# Sheet1.net
KiCad netlist of a schematic drawn in Altium Designer
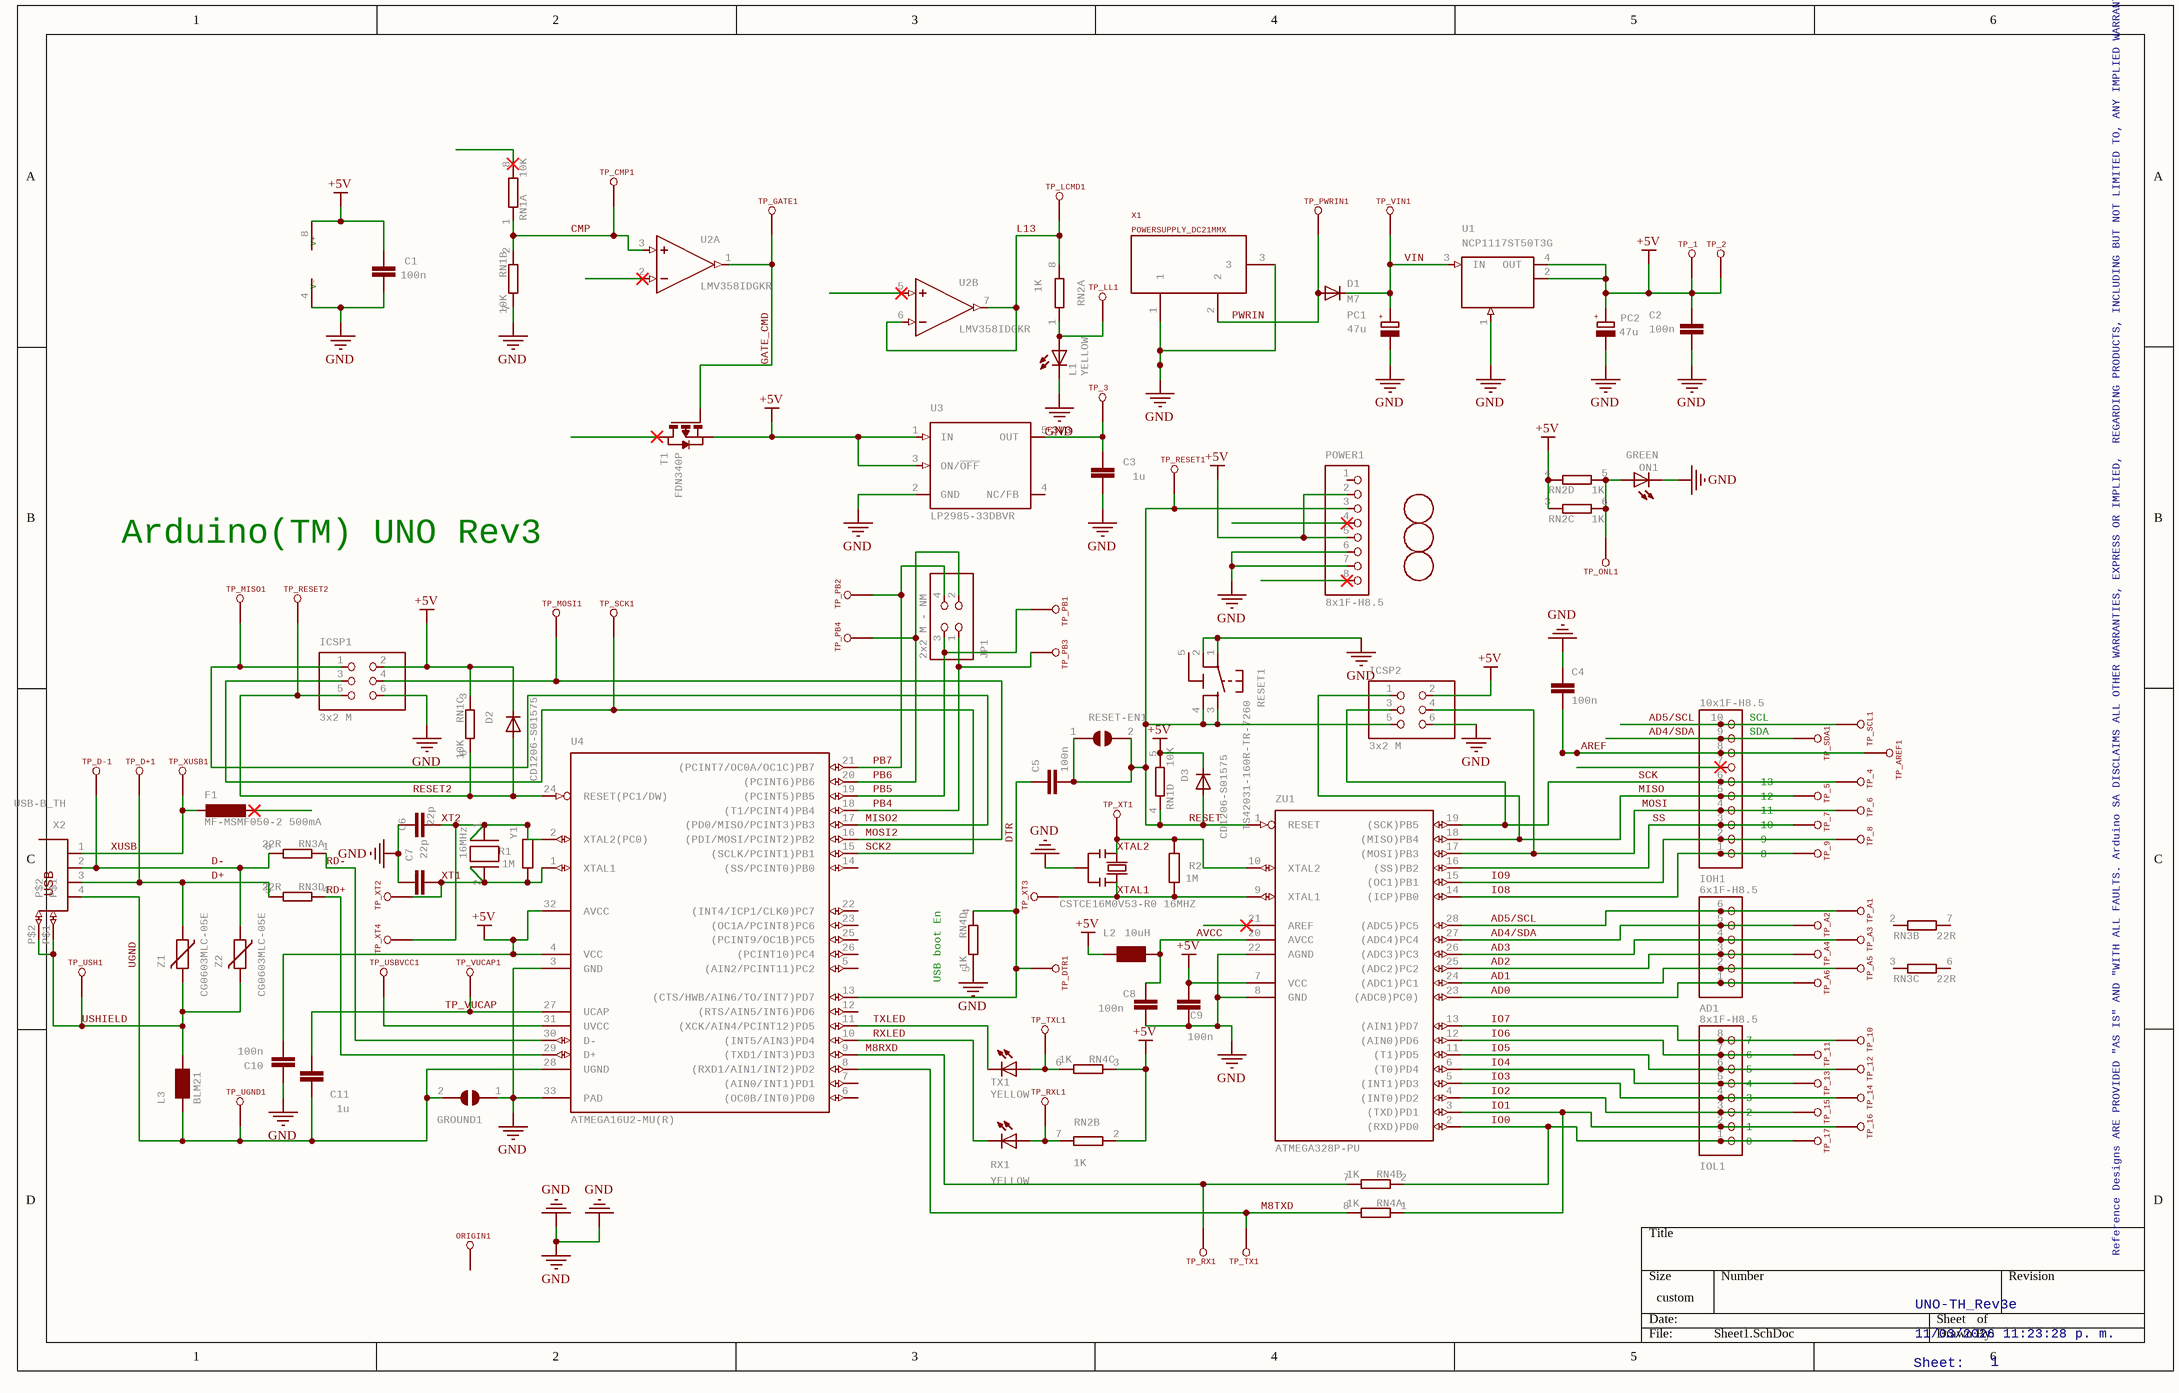
[diagram p0: Sheet1.SchDoc]

(export (version "E")
  (design (tool "Eeschema 10.0.6"))
  (components
    (comp (ref "AD1")
      (value "6x1F-H8.5")
      (footprint "1X06")
      (description "PIN HEADER")
      (libsource (lib "SmartPrj") (part "PINHD-1X6"))
    )
    (comp (ref "C1")
      (value "100n")
      (footprint "C0603-ROUND")
      (description "CAPACITOR, European symbol")
      (libsource (lib "") (part "C-EU0603-RND_1"))
    )
    (comp (ref "C2")
      (value "100n")
      (footprint "C0603-ROUND")
      (description "CAPACITOR, European symbol")
      (libsource (lib "") (part "C-EU0603-RND_2"))
    )
    (comp (ref "C3")
      (value "1u")
      (footprint "C0603-ROUND")
      (description "CAPACITOR, European symbol")
      (libsource (lib "") (part "C-EU0603-RND_1"))
    )
    (comp (ref "C4")
      (value "100n")
      (footprint "C0603-ROUND")
      (description "CAPACITOR, European symbol")
      (libsource (lib "SmartPrj") (part "C-EU0603-RND"))
    )
    (comp (ref "C5")
      (value "100n")
      (footprint "C0603-ROUND")
      (description "CAPACITOR, European symbol")
      (libsource (lib "") (part "C-EU0603-RND_1"))
    )
    (comp (ref "C6")
      (value "22p")
      (footprint "C0603-ROUND")
      (description "CAPACITOR, European symbol")
      (libsource (lib "SmartPrj") (part "C-EU0603-RND"))
    )
    (comp (ref "C7")
      (value "22p")
      (footprint "C0603-ROUND")
      (description "CAPACITOR, European symbol")
      (libsource (lib "SmartPrj") (part "C-EU0603-RND"))
    )
    (comp (ref "C8")
      (value "100n")
      (footprint "C0603-ROUND")
      (description "CAPACITOR, European symbol")
      (libsource (lib "") (part "C-EU0603-RND_2"))
    )
    (comp (ref "C9")
      (value "100n")
      (footprint "C0603-ROUND")
      (description "CAPACITOR, European symbol")
      (libsource (lib "") (part "C-EU0603-RND_2"))
    )
    (comp (ref "C10")
      (value "100n")
      (footprint "C0603-ROUND")
      (description "CAPACITOR, European symbol")
      (libsource (lib "") (part "C-EU0603-RND_3"))
    )
    (comp (ref "C11")
      (value "1u")
      (footprint "C0603-ROUND")
      (description "CAPACITOR, European symbol")
      (libsource (lib "") (part "C-EU0603-RND_3"))
    )
    (comp (ref "D1")
      (value "M7")
      (footprint "SMB")
      (description "DIODE")
      (libsource (lib "diode") (part "DIODE-SMB"))
    )
    (comp (ref "D2")
      (value "CD1206-S01575")
      (footprint "MINIMELF")
      (description "DIODE")
      (libsource (lib "diode") (part "DIODE-MINIMELF"))
    )
    (comp (ref "D3")
      (value "CD1206-S01575")
      (footprint "MINIMELF")
      (description "DIODE")
      (libsource (lib "diode") (part "DIODE-MINIMELF"))
    )
    (comp (ref "F1")
      (value "MF-MSMF050-2 500mA")
      (footprint "L1812")
      (description "INDUCTOR, European symbol")
      (libsource (lib "rcl") (part "L-EUL1812"))
    )
    (comp (ref "FD1")
      (value "FIDUCIALMOUNT")
      (footprint "FIDUCIA-MOUNT")
      (libsource (lib "SmartPrj") (part "FIDUCIALMOUNT"))
    )
    (comp (ref "FD2")
      (value "FIDUCIALMOUNT")
      (footprint "FIDUCIA-MOUNT")
      (libsource (lib "SmartPrj") (part "FIDUCIALMOUNT"))
    )
    (comp (ref "FD3")
      (value "FIDUCIALMOUNT")
      (footprint "FIDUCIA-MOUNT")
      (libsource (lib "SmartPrj") (part "FIDUCIALMOUNT"))
    )
    (comp (ref "GROUND1")
      (value "SJ")
      (footprint "SJ")
      (description "SMD solder JUMPER")
      (libsource (lib "jumper") (part "SJ"))
    )
    (comp (ref "ICSP1")
      (value "3x2 M")
      (footprint "2X03")
      (description "PIN HEADER")
      (libsource (lib "SmartPrj") (part "PINHD-2X3"))
    )
    (comp (ref "ICSP2")
      (value "3x2 M")
      (footprint "2X03")
      (description "PIN HEADER")
      (libsource (lib "SmartPrj") (part "PINHD-2X3"))
    )
    (comp (ref "IOH1")
      (value "10x1F-H8.5")
      (footprint "1X10")
      (description "PIN HEADER")
      (libsource (lib "SmartPrj") (part "PINHD-1X10_ARD"))
    )
    (comp (ref "IOL1")
      (value "8x1F-H8.5")
      (footprint "1X08")
      (description "PIN HEADER")
      (libsource (lib "SmartPrj") (part "PINHD-1X8"))
    )
    (comp (ref "JP1")
      (value "2x2 M - NM")
      (footprint "2X02")
      (description "PIN HEADER")
      (libsource (lib "SmartPrj") (part "PINHD-2X2"))
    )
    (comp (ref "L1")
      (value "YELLOW")
      (footprint "CHIP-LED0805")
      (libsource (lib "led") (part "LEDCHIP-LED0805"))
    )
    (comp (ref "L2")
      (value "10uH")
      (footprint "0805")
      (description "10uH 0805")
      (fields (field (name "PART_NUMBER") "CV201210-100K"))
      (libsource (lib "Induttanze") (part "0715_CV201210-100K"))
    )
    (comp (ref "L3")
      (value "BLM21")
      (footprint "0805")
      (libsource (lib "wuerth-elektronik") (part "WE-CBF_0805"))
    )
    (comp (ref "ON1")
      (value "GREEN")
      (footprint "CHIP-LED0805")
      (libsource (lib "led") (part "LEDCHIP-LED0805"))
    )
    (comp (ref "ORIGIN1") (value "TP_SP") (footprint "TP-SP") (libsource (lib "SmartPrj") (part "TP_SP")))
    (comp (ref "PC1")
      (value "47u")
      (footprint "PANASONIC_D")
      (description "POLARIZED CAPACITOR, European symbol")
      (fields (field (name "+") "+"))
      (libsource (lib "rcl") (part "CPOL-EUD"))
    )
    (comp (ref "PC2")
      (value "47u")
      (footprint "PANASONIC_D")
      (description "POLARIZED CAPACITOR, European symbol")
      (fields (field (name "+") "+"))
      (libsource (lib "rcl") (part "CPOL-EUD"))
    )
    (comp (ref "POWER1")
      (value "8x1F-H8.5")
      (footprint "1X08")
      (description "PIN HEADER")
      (libsource (lib "SmartPrj") (part "PINHD-1X8"))
    )
    (comp (ref "R1")
      (value "1M")
      (footprint "R0603-ROUND")
      (description "RESISTOR, European symbol")
      (libsource (lib "SmartPrj") (part "R-EU_R0603"))
    )
    (comp (ref "R2")
      (value "1M")
      (footprint "R0603-ROUND")
      (description "RESISTOR, European symbol")
      (libsource (lib "SmartPrj") (part "R-EU_R0603"))
    )
    (comp (ref "RESET-EN1")
      (value "SJ")
      (footprint "SJ")
      (description "SMD solder JUMPER")
      (libsource (lib "jumper") (part "SJ"))
    )
    (comp (ref "RESET1")
      (value "TS42031-160R-TR-7260")
      (footprint "TS42")
      (description "TS42 Dongnan Electronics Tact switch VDC 12V - 50mA")
      (libsource (lib "SmartPrj") (part "TS42"))
    )
    (comp (ref "RN1")
      (value "10K")
      (footprint "CAY16")
      (description "Array Chip Resistor   Source: RS Component / Phycomp")
      (libsource (lib "resistor-dil") (part "4R-NCAY16"))
    )
    (comp (ref "RN2")
      (value "1K")
      (footprint "CAY16")
      (description "Array Chip Resistor   Source: RS Component / Phycomp")
      (libsource (lib "resistor-dil") (part "4R-NCAY16"))
    )
    (comp (ref "RN3")
      (value "22R")
      (footprint "CAY16")
      (description "Array Chip Resistor   Source: RS Component / Phycomp")
      (libsource (lib "resistor-dil") (part "4R-NCAY16"))
    )
    (comp (ref "RN4")
      (value "1K")
      (footprint "CAY16")
      (description "Array Chip Resistor   Source: RS Component / Phycomp")
      (libsource (lib "resistor-dil") (part "4R-NCAY16"))
    )
    (comp (ref "RX1")
      (value "YELLOW")
      (footprint "CHIP-LED0805")
      (libsource (lib "led") (part "LEDCHIP-LED0805"))
    )
    (comp (ref "T1")
      (value "FDN340P")
      (footprint "SOT-23")
      (description "MOS FET")
      (libsource (lib "zetex") (part "PMOSSOT23"))
    )
    (comp (ref "TP_1") (value "TP_SP") (footprint "TP-SP") (libsource (lib "SmartPrj") (part "TP_SP")))
    (comp (ref "TP_2") (value "TP_SP") (footprint "TP-SP") (libsource (lib "SmartPrj") (part "TP_SP")))
    (comp (ref "TP_3") (value "TP_SP") (footprint "TP-SP") (libsource (lib "SmartPrj") (part "TP_SP")))
    (comp (ref "TP_4") (value "TP_SP") (footprint "TP-SP") (libsource (lib "SmartPrj") (part "TP_SP")))
    (comp (ref "TP_5") (value "TP_SP") (footprint "TP-SP") (libsource (lib "SmartPrj") (part "TP_SP")))
    (comp (ref "TP_6") (value "TP_SP") (footprint "TP-SP") (libsource (lib "SmartPrj") (part "TP_SP")))
    (comp (ref "TP_7") (value "TP_SP") (footprint "TP-SP") (libsource (lib "SmartPrj") (part "TP_SP")))
    (comp (ref "TP_8") (value "TP_SP") (footprint "TP-SP") (libsource (lib "SmartPrj") (part "TP_SP")))
    (comp (ref "TP_9") (value "TP_SP") (footprint "TP-SP") (libsource (lib "SmartPrj") (part "TP_SP")))
    (comp (ref "TP_10") (value "TP_SP") (footprint "TP-SP") (libsource (lib "SmartPrj") (part "TP_SP")))
    (comp (ref "TP_11") (value "TP_SP") (footprint "TP-SP") (libsource (lib "SmartPrj") (part "TP_SP")))
    (comp (ref "TP_12") (value "TP_SP") (footprint "TP-SP") (libsource (lib "SmartPrj") (part "TP_SP")))
    (comp (ref "TP_13") (value "TP_SP") (footprint "TP-SP") (libsource (lib "SmartPrj") (part "TP_SP")))
    (comp (ref "TP_14") (value "TP_SP") (footprint "TP-SP") (libsource (lib "SmartPrj") (part "TP_SP")))
    (comp (ref "TP_15") (value "TP_SP") (footprint "TP-SP") (libsource (lib "SmartPrj") (part "TP_SP")))
    (comp (ref "TP_16") (value "TP_SP") (footprint "TP-SP") (libsource (lib "SmartPrj") (part "TP_SP")))
    (comp (ref "TP_17") (value "TP_SP") (footprint "TP-SP") (libsource (lib "SmartPrj") (part "TP_SP")))
    (comp (ref "TP_A1") (value "TP_SP") (footprint "TP-SP") (libsource (lib "SmartPrj") (part "TP_SP")))
    (comp (ref "TP_A2") (value "TP_SP") (footprint "TP-SP") (libsource (lib "SmartPrj") (part "TP_SP")))
    (comp (ref "TP_A3") (value "TP_SP") (footprint "TP-SP") (libsource (lib "SmartPrj") (part "TP_SP")))
    (comp (ref "TP_A4") (value "TP_SP") (footprint "TP-SP") (libsource (lib "SmartPrj") (part "TP_SP")))
    (comp (ref "TP_A5") (value "TP_SP") (footprint "TP-SP") (libsource (lib "SmartPrj") (part "TP_SP")))
    (comp (ref "TP_A6") (value "TP_SP") (footprint "TP-SP") (libsource (lib "SmartPrj") (part "TP_SP")))
    (comp (ref "TP_AREF1") (value "TP_SP") (footprint "TP-SP") (libsource (lib "SmartPrj") (part "TP_SP")))
    (comp (ref "TP_CMP1") (value "TP_SP") (footprint "TP-SP") (libsource (lib "SmartPrj") (part "TP_SP")))
    (comp (ref "TP_D+1") (value "TP_SP") (footprint "TP-SP") (libsource (lib "SmartPrj") (part "TP_SP")))
    (comp (ref "TP_D-1") (value "TP_SP") (footprint "TP-SP") (libsource (lib "SmartPrj") (part "TP_SP")))
    (comp (ref "TP_DTR1") (value "TP_SP") (footprint "TP-SP") (libsource (lib "SmartPrj") (part "TP_SP")))
    (comp (ref "TP_GATE1") (value "TP_SP") (footprint "TP-SP") (libsource (lib "SmartPrj") (part "TP_SP")))
    (comp (ref "TP_LCMD1") (value "TP_SP") (footprint "TP-SP") (libsource (lib "SmartPrj") (part "TP_SP")))
    (comp (ref "TP_LL1") (value "TP_SP") (footprint "TP-SP") (libsource (lib "SmartPrj") (part "TP_SP")))
    (comp (ref "TP_MISO1") (value "TP_SP") (footprint "TP-SP") (libsource (lib "SmartPrj") (part "TP_SP")))
    (comp (ref "TP_MOSI1") (value "TP_SP") (footprint "TP-SP") (libsource (lib "SmartPrj") (part "TP_SP")))
    (comp (ref "TP_ONL1") (value "TP_SP") (footprint "TP-SP") (libsource (lib "SmartPrj") (part "TP_SP")))
    (comp (ref "TP_PB1") (value "TP_SP") (footprint "TP-SP") (libsource (lib "SmartPrj") (part "TP_SP")))
    (comp (ref "TP_PB2") (value "TP_SP") (footprint "TP-SP") (libsource (lib "SmartPrj") (part "TP_SP")))
    (comp (ref "TP_PB3") (value "TP_SP") (footprint "TP-SP") (libsource (lib "SmartPrj") (part "TP_SP")))
    (comp (ref "TP_PB4") (value "TP_SP") (footprint "TP-SP") (libsource (lib "SmartPrj") (part "TP_SP")))
    (comp (ref "TP_PWRIN1") (value "TP_SP") (footprint "TP-SP") (libsource (lib "SmartPrj") (part "TP_SP")))
    (comp (ref "TP_RESET1") (value "TP_SP") (footprint "TP-SP") (libsource (lib "SmartPrj") (part "TP_SP")))
    (comp (ref "TP_RESET2") (value "TP_SP") (footprint "TP-SP") (libsource (lib "SmartPrj") (part "TP_SP")))
    (comp (ref "TP_RX1") (value "TP_SP") (footprint "TP-SP") (libsource (lib "SmartPrj") (part "TP_SP")))
    (comp (ref "TP_RXL1") (value "TP_SP") (footprint "TP-SP") (libsource (lib "SmartPrj") (part "TP_SP")))
    (comp (ref "TP_SCK1") (value "TP_SP") (footprint "TP-SP") (libsource (lib "SmartPrj") (part "TP_SP")))
    (comp (ref "TP_SCL1") (value "TP_SP") (footprint "TP-SP") (libsource (lib "SmartPrj") (part "TP_SP")))
    (comp (ref "TP_SDA1") (value "TP_SP") (footprint "TP-SP") (libsource (lib "SmartPrj") (part "TP_SP")))
    (comp (ref "TP_TX1") (value "TP_SP") (footprint "TP-SP") (libsource (lib "SmartPrj") (part "TP_SP")))
    (comp (ref "TP_TXL1") (value "TP_SP") (footprint "TP-SP") (libsource (lib "SmartPrj") (part "TP_SP")))
    (comp (ref "TP_UGND1") (value "TP_SP") (footprint "TP-SP") (libsource (lib "SmartPrj") (part "TP_SP")))
    (comp (ref "TP_USBVCC1") (value "TP_SP") (footprint "TP-SP") (libsource (lib "SmartPrj") (part "TP_SP")))
    (comp (ref "TP_USH1") (value "TP_SP") (footprint "TP-SP") (libsource (lib "SmartPrj") (part "TP_SP")))
    (comp (ref "TP_VIN1") (value "TP_SP") (footprint "TP-SP") (libsource (lib "SmartPrj") (part "TP_SP")))
    (comp (ref "TP_VUCAP1") (value "TP_SP") (footprint "TP-SP") (libsource (lib "SmartPrj") (part "TP_SP")))
    (comp (ref "TP_XT1") (value "TP_SP") (footprint "TP-SP") (libsource (lib "SmartPrj") (part "TP_SP")))
    (comp (ref "TP_XT2") (value "TP_SP") (footprint "TP-SP") (libsource (lib "SmartPrj") (part "TP_SP")))
    (comp (ref "TP_XT3") (value "TP_SP") (footprint "TP-SP") (libsource (lib "SmartPrj") (part "TP_SP")))
    (comp (ref "TP_XT4") (value "TP_SP") (footprint "TP-SP") (libsource (lib "SmartPrj") (part "TP_SP")))
    (comp (ref "TP_XUSB1") (value "TP_SP") (footprint "TP-SP") (libsource (lib "SmartPrj") (part "TP_SP")))
    (comp (ref "TX1")
      (value "YELLOW")
      (footprint "CHIP-LED0805")
      (libsource (lib "led") (part "LEDCHIP-LED0805"))
    )
    (comp (ref "U1")
      (value "NCP1117ST50T3G")
      (footprint "SOT223")
      (libsource (lib "linear") (part "MC33269ST*"))
    )
    (comp (ref "U2")
      (value "LMV358IDGKR")
      (footprint "MSOP08")
      (fields (field (name "V+") "V+") (field (name "V-") "V-"))
      (libsource (lib "linear") (part "LMV358?*MM"))
    )
    (comp (ref "U3")
      (value "LP2985-33DBVR")
      (footprint "SOT23-DBV")
      (libsource (lib "SmartPrj") (part "LP2985-XXDBVR"))
    )
    (comp (ref "U4")
      (value "ATMEGA16U2-MU(R)")
      (footprint "MLF32")
      (libsource (lib "SmartPrj") (part "ATMEGA16U2-MU"))
    )
    (comp (ref "X1")
      (value "POWERSUPPLY_DC21MMX")
      (footprint "POWERSUPPLY_DC-21MM")
      (libsource (lib "SmartPrj") (part "POWERSUPPLY_DC21MMX"))
    )
    (comp (ref "X2")
      (value "USB-B_TH")
      (footprint "PN61729")
      (description "BERG USB connector")
      (fields (field (name "USB") "USB"))
      (libsource (lib "SmartPrj") (part "PN61729"))
    )
    (comp (ref "Y1")
      (value "16MHz")
      (footprint "QS")
      (description "CRYSTAL")
      (libsource (lib "SmartPrj") (part "XTAL/S"))
    )
    (comp (ref "Y2")
      (value "CSTCE16M0V53-R0 16MHZ")
      (footprint "RESONATOR")
      (libsource (lib "SmartPrj") (part "RESONATORMU"))
    )
    (comp (ref "Z1")
      (value "CG0603MLC-05E")
      (footprint "CT/CN0603")
      (description "VARISTOR")
      (libsource (lib "varistor") (part "VARISTORCN0603"))
    )
    (comp (ref "Z2")
      (value "CG0603MLC-05E")
      (footprint "CT/CN0603")
      (description "VARISTOR")
      (libsource (lib "varistor") (part "VARISTORCN0603"))
    )
    (comp (ref "ZU1")
      (value "ATMEGA328P-PU")
      (footprint "DIL28-3")
      (description "MICROCONTROLLER   4 Kbytes FLASH   128 bytes SRAM   256 bytes EEPROM   UART   6-channel 10 bit ADC")
      (libsource (lib "SmartPrj") (part "ATMEGA328P-PU"))
    )
  )
  (nets
    (net (code "1") (name "+5V") (class "Default")
      (node (ref "C1") (pin "2") (pinfunction "2_2") (pintype "passive"))
      (node (ref "C10") (pin "1") (pinfunction "1_1") (pintype "passive"))
      (node (ref "C2") (pin "2") (pinfunction "2_2") (pintype "passive"))
      (node (ref "C9") (pin "2") (pinfunction "2_2") (pintype "passive"))
      (node (ref "D2") (pin "C") (pinfunction "C_C") (pintype "passive"))
      (node (ref "D3") (pin "C") (pinfunction "C_C") (pintype "passive"))
      (node (ref "ICSP1") (pin "2") (pinfunction "2_2") (pintype "passive"))
      (node (ref "ICSP2") (pin "2") (pinfunction "2_2") (pintype "passive"))
      (node (ref "L2") (pin "1") (pinfunction "1_1") (pintype "passive"))
      (node (ref "PC2") (pin "+") (pinfunction "+_+") (pintype "passive"))
      (node (ref "POWER1") (pin "2") (pinfunction "2_2") (pintype "passive"))
      (node (ref "POWER1") (pin "5") (pinfunction "5_5") (pintype "passive"))
      (node (ref "RN1") (pin "3") (pinfunction "1_3") (pintype "passive"))
      (node (ref "RN1") (pin "5") (pinfunction "2_5") (pintype "passive"))
      (node (ref "RN2") (pin "2") (pinfunction "1_2") (pintype "passive"))
      (node (ref "RN2") (pin "3") (pinfunction "1_3") (pintype "passive"))
      (node (ref "RN2") (pin "4") (pinfunction "1_4") (pintype "passive"))
      (node (ref "RN4") (pin "3") (pinfunction "1_3") (pintype "passive"))
      (node (ref "T1") (pin "2") (pinfunction "S_2") (pintype "passive"))
      (node (ref "TP_1") (pin "X") (pinfunction "TESTP_X") (pintype "passive"))
      (node (ref "TP_2") (pin "X") (pinfunction "TESTP_X") (pintype "passive"))
      (node (ref "U1") (pin "2") (pinfunction "OUT_2") (pintype "passive"))
      (node (ref "U1") (pin "4") (pinfunction "OUT_4") (pintype "passive"))
      (node (ref "U2") (pin "8") (pinfunction "V+_8") (pintype "power_in"))
      (node (ref "U3") (pin "1") (pinfunction "IN_1") (pintype "input"))
      (node (ref "U3") (pin "3") (pinfunction "ON/~{OFF}_3") (pintype "input"))
      (node (ref "U4") (pin "32") (pinfunction "AVCC_32") (pintype "power_in"))
      (node (ref "U4") (pin "4") (pinfunction "VCC_4") (pintype "power_in"))
      (node (ref "ZU1") (pin "7") (pinfunction "VCC_7") (pintype "power_in"))
    )
    (net (code "2") (name "/+3V3") (class "Default")
      (node (ref "C3") (pin "2") (pinfunction "2_2") (pintype "passive"))
      (node (ref "TP_3") (pin "X") (pinfunction "TESTP_X") (pintype "passive"))
      (node (ref "U3") (pin "5") (pinfunction "OUT_5") (pintype "passive"))
    )
    (net (code "3") (name "/AD0") (class "Default")
      (node (ref "AD1") (pin "1") (pinfunction "1_1") (pintype "passive"))
      (node (ref "TP_A6") (pin "X") (pinfunction "TESTP_X") (pintype "passive"))
      (node (ref "ZU1") (pin "23") (pinfunction "(ADC0)PC0)_23") (pintype "bidirectional"))
    )
    (net (code "4") (name "/AD1") (class "Default")
      (node (ref "AD1") (pin "2") (pinfunction "2_2") (pintype "passive"))
      (node (ref "TP_A5") (pin "X") (pinfunction "TESTP_X") (pintype "passive"))
      (node (ref "ZU1") (pin "24") (pinfunction "(ADC1)PC1_24") (pintype "bidirectional"))
    )
    (net (code "5") (name "/AD2") (class "Default")
      (node (ref "AD1") (pin "3") (pinfunction "3_3") (pintype "passive"))
      (node (ref "TP_A4") (pin "X") (pinfunction "TESTP_X") (pintype "passive"))
      (node (ref "ZU1") (pin "25") (pinfunction "(ADC2)PC2_25") (pintype "bidirectional"))
    )
    (net (code "6") (name "/AD3") (class "Default")
      (node (ref "AD1") (pin "4") (pinfunction "4_4") (pintype "passive"))
      (node (ref "TP_A3") (pin "X") (pinfunction "TESTP_X") (pintype "passive"))
      (node (ref "ZU1") (pin "26") (pinfunction "(ADC3)PC3_26") (pintype "bidirectional"))
    )
    (net (code "7") (name "/AD4{slash}SDA") (class "Default")
      (node (ref "AD1") (pin "5") (pinfunction "5_5") (pintype "passive"))
      (node (ref "IOH1") (pin "9") (pinfunction "9_9") (pintype "passive"))
      (node (ref "TP_A2") (pin "X") (pinfunction "TESTP_X") (pintype "passive"))
      (node (ref "TP_SDA1") (pin "X") (pinfunction "TESTP_X") (pintype "passive"))
      (node (ref "ZU1") (pin "27") (pinfunction "(ADC4)PC4_27") (pintype "bidirectional"))
    )
    (net (code "8") (name "/AD5{slash}SCL") (class "Default")
      (node (ref "AD1") (pin "6") (pinfunction "6_6") (pintype "passive"))
      (node (ref "IOH1") (pin "10") (pinfunction "10_10") (pintype "passive"))
      (node (ref "TP_A1") (pin "X") (pinfunction "TESTP_X") (pintype "passive"))
      (node (ref "TP_SCL1") (pin "X") (pinfunction "TESTP_X") (pintype "passive"))
      (node (ref "ZU1") (pin "28") (pinfunction "(ADC5)PC5_28") (pintype "bidirectional"))
    )
    (net (code "9") (name "/AREF") (class "Default")
      (node (ref "C4") (pin "2") (pinfunction "2_2") (pintype "passive"))
      (node (ref "IOH1") (pin "8") (pinfunction "8_8") (pintype "passive"))
      (node (ref "TP_AREF1") (pin "X") (pinfunction "TESTP_X") (pintype "passive"))
    )
    (net (code "10") (name "/AVCC") (class "Default")
      (node (ref "C8") (pin "2") (pinfunction "2_2") (pintype "passive"))
      (node (ref "L2") (pin "2") (pinfunction "2_2") (pintype "passive"))
      (node (ref "ZU1") (pin "20") (pinfunction "AVCC_20") (pintype "power_in"))
    )
    (net (code "11") (name "/CMP") (class "Default")
      (node (ref "RN1") (pin "1") (pinfunction "1_1") (pintype "passive"))
      (node (ref "RN1") (pin "2") (pinfunction "1_2") (pintype "passive"))
      (node (ref "TP_CMP1") (pin "X") (pinfunction "TESTP_X") (pintype "passive"))
      (node (ref "U2") (pin "3") (pinfunction "+IN_3") (pintype "input"))
    )
    (net (code "12") (name "/D+") (class "Default")
      (node (ref "RN3") (pin "5") (pinfunction "2_5") (pintype "passive"))
      (node (ref "TP_D+1") (pin "X") (pinfunction "TESTP_X") (pintype "passive"))
      (node (ref "X2") (pin "3") (pinfunction "3_3") (pintype "bidirectional"))
      (node (ref "Z1") (pin "1") (pinfunction "1_1") (pintype "passive"))
    )
    (net (code "13") (name "/D-") (class "Default")
      (node (ref "RN3") (pin "8") (pinfunction "2_8") (pintype "passive"))
      (node (ref "TP_D-1") (pin "X") (pinfunction "TESTP_X") (pintype "passive"))
      (node (ref "X2") (pin "2") (pinfunction "2_2") (pintype "bidirectional"))
      (node (ref "Z2") (pin "1") (pinfunction "1_1") (pintype "passive"))
    )
    (net (code "14") (name "/DTR") (class "Default")
      (node (ref "C5") (pin "1") (pinfunction "1_1") (pintype "passive"))
      (node (ref "RN4") (pin "4") (pinfunction "1_4") (pintype "passive"))
      (node (ref "TP_DTR1") (pin "X") (pinfunction "TESTP_X") (pintype "passive"))
      (node (ref "U4") (pin "13") (pinfunction "(CTS/HWB/AIN6/TO/INT7)PD7_13") (pintype "bidirectional"))
    )
    (net (code "15") (name "/GATE_CMD") (class "Default")
      (node (ref "T1") (pin "3") (pinfunction "G_3") (pintype "passive"))
      (node (ref "TP_GATE1") (pin "X") (pinfunction "TESTP_X") (pintype "passive"))
      (node (ref "U2") (pin "1") (pinfunction "OUT_1") (pintype "output"))
    )
    (net (code "16") (name "/IO0") (class "Default")
      (node (ref "IOL1") (pin "1") (pinfunction "1_1") (pintype "passive"))
      (node (ref "RN4") (pin "2") (pinfunction "1_2") (pintype "passive"))
      (node (ref "TP_17") (pin "X") (pinfunction "TESTP_X") (pintype "passive"))
      (node (ref "ZU1") (pin "2") (pinfunction "(RXD)PD0_2") (pintype "bidirectional"))
    )
    (net (code "17") (name "/IO1") (class "Default")
      (node (ref "IOL1") (pin "2") (pinfunction "2_2") (pintype "passive"))
      (node (ref "RN4") (pin "1") (pinfunction "1_1") (pintype "passive"))
      (node (ref "TP_16") (pin "X") (pinfunction "TESTP_X") (pintype "passive"))
      (node (ref "ZU1") (pin "3") (pinfunction "(TXD)PD1_3") (pintype "bidirectional"))
    )
    (net (code "18") (name "/IO2") (class "Default")
      (node (ref "IOL1") (pin "3") (pinfunction "3_3") (pintype "passive"))
      (node (ref "TP_15") (pin "X") (pinfunction "TESTP_X") (pintype "passive"))
      (node (ref "ZU1") (pin "4") (pinfunction "(INT0)PD2_4") (pintype "bidirectional"))
    )
    (net (code "19") (name "/IO3") (class "Default")
      (node (ref "IOL1") (pin "4") (pinfunction "4_4") (pintype "passive"))
      (node (ref "TP_14") (pin "X") (pinfunction "TESTP_X") (pintype "passive"))
      (node (ref "ZU1") (pin "5") (pinfunction "(INT1)PD3_5") (pintype "bidirectional"))
    )
    (net (code "20") (name "/IO4") (class "Default")
      (node (ref "IOL1") (pin "5") (pinfunction "5_5") (pintype "passive"))
      (node (ref "TP_13") (pin "X") (pinfunction "TESTP_X") (pintype "passive"))
      (node (ref "ZU1") (pin "6") (pinfunction "(T0)PD4_6") (pintype "bidirectional"))
    )
    (net (code "21") (name "/IO5") (class "Default")
      (node (ref "IOL1") (pin "6") (pinfunction "6_6") (pintype "passive"))
      (node (ref "TP_12") (pin "X") (pinfunction "TESTP_X") (pintype "passive"))
      (node (ref "ZU1") (pin "11") (pinfunction "(T1)PD5_11") (pintype "bidirectional"))
    )
    (net (code "22") (name "/IO6") (class "Default")
      (node (ref "IOL1") (pin "7") (pinfunction "7_7") (pintype "passive"))
      (node (ref "TP_11") (pin "X") (pinfunction "TESTP_X") (pintype "passive"))
      (node (ref "ZU1") (pin "12") (pinfunction "(AIN0)PD6_12") (pintype "bidirectional"))
    )
    (net (code "23") (name "/IO7") (class "Default")
      (node (ref "IOL1") (pin "8") (pinfunction "8_8") (pintype "passive"))
      (node (ref "TP_10") (pin "X") (pinfunction "TESTP_X") (pintype "passive"))
      (node (ref "ZU1") (pin "13") (pinfunction "(AIN1)PD7_13") (pintype "bidirectional"))
    )
    (net (code "24") (name "/IO8") (class "Default")
      (node (ref "IOH1") (pin "1") (pinfunction "1_1") (pintype "passive"))
      (node (ref "TP_9") (pin "X") (pinfunction "TESTP_X") (pintype "passive"))
      (node (ref "ZU1") (pin "14") (pinfunction "(ICP)PB0_14") (pintype "bidirectional"))
    )
    (net (code "25") (name "/IO9") (class "Default")
      (node (ref "IOH1") (pin "2") (pinfunction "2_2") (pintype "passive"))
      (node (ref "TP_8") (pin "X") (pinfunction "TESTP_X") (pintype "passive"))
      (node (ref "ZU1") (pin "15") (pinfunction "(OC1)PB1_15") (pintype "bidirectional"))
    )
    (net (code "26") (name "/L13") (class "Default")
      (node (ref "RN2") (pin "8") (pinfunction "2_8") (pintype "passive"))
      (node (ref "TP_LCMD1") (pin "X") (pinfunction "TESTP_X") (pintype "passive"))
      (node (ref "U2") (pin "6") (pinfunction "-IN_6") (pintype "input"))
      (node (ref "U2") (pin "7") (pinfunction "OUT_7") (pintype "output"))
    )
    (net (code "27") (name "/M8RXD") (class "Default")
      (node (ref "RN4") (pin "7") (pinfunction "2_7") (pintype "passive"))
      (node (ref "TP_RX1") (pin "X") (pinfunction "TESTP_X") (pintype "passive"))
      (node (ref "U4") (pin "9") (pinfunction "(TXD1/INT3)PD3_9") (pintype "bidirectional"))
    )
    (net (code "28") (name "/M8TXD") (class "Default")
      (node (ref "RN4") (pin "8") (pinfunction "2_8") (pintype "passive"))
      (node (ref "TP_TX1") (pin "X") (pinfunction "TESTP_X") (pintype "passive"))
      (node (ref "U4") (pin "8") (pinfunction "(RXD1/AIN1/INT2)PD2_8") (pintype "bidirectional"))
    )
    (net (code "29") (name "/MISO") (class "Default")
      (node (ref "ICSP2") (pin "1") (pinfunction "1_1") (pintype "passive"))
      (node (ref "IOH1") (pin "5") (pinfunction "5_5") (pintype "passive"))
      (node (ref "TP_5") (pin "X") (pinfunction "TESTP_X") (pintype "passive"))
      (node (ref "ZU1") (pin "18") (pinfunction "(MISO)PB4_18") (pintype "bidirectional"))
    )
    (net (code "30") (name "/MISO2") (class "Default")
      (node (ref "ICSP1") (pin "1") (pinfunction "1_1") (pintype "passive"))
      (node (ref "TP_MISO1") (pin "X") (pinfunction "TESTP_X") (pintype "passive"))
      (node (ref "U4") (pin "17") (pinfunction "(PD0/MISO/PCINT3)PB3_17") (pintype "bidirectional"))
    )
    (net (code "31") (name "/MOSI") (class "Default")
      (node (ref "ICSP2") (pin "4") (pinfunction "4_4") (pintype "passive"))
      (node (ref "IOH1") (pin "4") (pinfunction "4_4") (pintype "passive"))
      (node (ref "TP_6") (pin "X") (pinfunction "TESTP_X") (pintype "passive"))
      (node (ref "ZU1") (pin "17") (pinfunction "(MOSI)PB3_17") (pintype "bidirectional"))
    )
    (net (code "32") (name "/MOSI2") (class "Default")
      (node (ref "ICSP1") (pin "4") (pinfunction "4_4") (pintype "passive"))
      (node (ref "TP_MOSI1") (pin "X") (pinfunction "TESTP_X") (pintype "passive"))
      (node (ref "U4") (pin "16") (pinfunction "(PDI/MOSI/PCINT2)PB2_16") (pintype "bidirectional"))
    )
    (net (code "33") (name "/PB4") (class "Default")
      (node (ref "JP1") (pin "1") (pinfunction "1_1") (pintype "passive"))
      (node (ref "TP_PB3") (pin "X") (pinfunction "TESTP_X") (pintype "passive"))
      (node (ref "U4") (pin "18") (pinfunction "(T1/PCINT4)PB4_18") (pintype "bidirectional"))
    )
    (net (code "34") (name "/PB5") (class "Default")
      (node (ref "JP1") (pin "3") (pinfunction "3_3") (pintype "passive"))
      (node (ref "TP_PB1") (pin "X") (pinfunction "TESTP_X") (pintype "passive"))
      (node (ref "U4") (pin "19") (pinfunction "(PCINT5)PB5_19") (pintype "bidirectional"))
    )
    (net (code "35") (name "/PB6") (class "Default")
      (node (ref "JP1") (pin "2") (pinfunction "2_2") (pintype "passive"))
      (node (ref "TP_PB4") (pin "X") (pinfunction "TESTP_X") (pintype "passive"))
      (node (ref "U4") (pin "20") (pinfunction "(PCINT6)PB6_20") (pintype "bidirectional"))
    )
    (net (code "36") (name "/PB7") (class "Default")
      (node (ref "JP1") (pin "4") (pinfunction "4_4") (pintype "passive"))
      (node (ref "TP_PB2") (pin "X") (pinfunction "TESTP_X") (pintype "passive"))
      (node (ref "U4") (pin "21") (pinfunction "(PCINT7/OC0A/OC1C)PB7_21") (pintype "bidirectional"))
    )
    (net (code "37") (name "/PWRIN") (class "Default")
      (node (ref "D1") (pin "A") (pinfunction "A_A") (pintype "passive"))
      (node (ref "TP_PWRIN1") (pin "X") (pinfunction "TESTP_X") (pintype "passive"))
      (node (ref "X1") (pin "2") (pinfunction "2_2") (pintype "power_in"))
    )
    (net (code "38") (name "/RD+") (class "Default")
      (node (ref "RN3") (pin "4") (pinfunction "1_4") (pintype "passive"))
      (node (ref "U4") (pin "29") (pinfunction "D+_29") (pintype "bidirectional"))
    )
    (net (code "39") (name "/RD-") (class "Default")
      (node (ref "RN3") (pin "1") (pinfunction "1_1") (pintype "passive"))
      (node (ref "U4") (pin "30") (pinfunction "D-_30") (pintype "bidirectional"))
    )
    (net (code "40") (name "/RESET") (class "Default")
      (node (ref "C5") (pin "2") (pinfunction "2_2") (pintype "passive"))
      (node (ref "D3") (pin "A") (pinfunction "A_A") (pintype "passive"))
      (node (ref "ICSP2") (pin "5") (pinfunction "5_5") (pintype "passive"))
      (node (ref "POWER1") (pin "3") (pinfunction "3_3") (pintype "passive"))
      (node (ref "RESET-EN1") (pin "1") (pinfunction "1_1") (pintype "passive"))
      (node (ref "RESET-EN1") (pin "2") (pinfunction "2_2") (pintype "passive"))
      (node (ref "RESET1") (pin "3") (pinfunction "3_3") (pintype "passive"))
      (node (ref "RESET1") (pin "4") (pinfunction "4_4") (pintype "passive"))
      (node (ref "RN1") (pin "4") (pinfunction "1_4") (pintype "passive"))
      (node (ref "TP_RESET1") (pin "X") (pinfunction "TESTP_X") (pintype "passive"))
      (node (ref "ZU1") (pin "1") (pinfunction "RESET_1") (pintype "input"))
    )
    (net (code "41") (name "/RESET2") (class "Default")
      (node (ref "D2") (pin "A") (pinfunction "A_A") (pintype "passive"))
      (node (ref "ICSP1") (pin "5") (pinfunction "5_5") (pintype "passive"))
      (node (ref "RN1") (pin "6") (pinfunction "2_6") (pintype "passive"))
      (node (ref "TP_RESET2") (pin "X") (pinfunction "TESTP_X") (pintype "passive"))
      (node (ref "U4") (pin "24") (pinfunction "RESET(PC1/DW)_24") (pintype "input"))
    )
    (net (code "42") (name "/RXLED") (class "Default")
      (node (ref "RX1") (pin "C") (pinfunction "C_C") (pintype "passive"))
      (node (ref "U4") (pin "10") (pinfunction "(INT5/AIN3)PD4_10") (pintype "bidirectional"))
    )
    (net (code "43") (name "/SCK") (class "Default")
      (node (ref "ICSP2") (pin "3") (pinfunction "3_3") (pintype "passive"))
      (node (ref "IOH1") (pin "6") (pinfunction "6_6") (pintype "passive"))
      (node (ref "TP_4") (pin "X") (pinfunction "TESTP_X") (pintype "passive"))
      (node (ref "ZU1") (pin "19") (pinfunction "(SCK)PB5_19") (pintype "bidirectional"))
    )
    (net (code "44") (name "/SCK2") (class "Default")
      (node (ref "ICSP1") (pin "3") (pinfunction "3_3") (pintype "passive"))
      (node (ref "TP_SCK1") (pin "X") (pinfunction "TESTP_X") (pintype "passive"))
      (node (ref "U4") (pin "15") (pinfunction "(SCLK/PCINT1)PB1_15") (pintype "bidirectional"))
    )
    (net (code "45") (name "/SS") (class "Default")
      (node (ref "IOH1") (pin "3") (pinfunction "3_3") (pintype "passive"))
      (node (ref "TP_7") (pin "X") (pinfunction "TESTP_X") (pintype "passive"))
      (node (ref "ZU1") (pin "16") (pinfunction "(SS)PB2_16") (pintype "bidirectional"))
    )
    (net (code "46") (name "/TP_VUCAP") (class "Default")
      (node (ref "C11") (pin "1") (pinfunction "1_1") (pintype "passive"))
      (node (ref "TP_VUCAP1") (pin "X") (pinfunction "TESTP_X") (pintype "passive"))
      (node (ref "U4") (pin "27") (pinfunction "UCAP_27") (pintype "passive"))
    )
    (net (code "47") (name "/TXLED") (class "Default")
      (node (ref "TX1") (pin "C") (pinfunction "C_C") (pintype "passive"))
      (node (ref "U4") (pin "11") (pinfunction "(XCK/AIN4/PCINT12)PD5_11") (pintype "bidirectional"))
    )
    (net (code "48") (name "/UGND") (class "Default")
      (node (ref "C11") (pin "2") (pinfunction "2_2") (pintype "passive"))
      (node (ref "GROUND1") (pin "2") (pinfunction "2_2") (pintype "passive"))
      (node (ref "L3") (pin "1") (pinfunction "1_1") (pintype "passive"))
      (node (ref "TP_UGND1") (pin "X") (pinfunction "TESTP_X") (pintype "passive"))
      (node (ref "U4") (pin "28") (pinfunction "UGND_28") (pintype "power_in"))
      (node (ref "X2") (pin "4") (pinfunction "4_4") (pintype "bidirectional"))
    )
    (net (code "49") (name "/USHIELD") (class "Default")
      (node (ref "L3") (pin "2") (pinfunction "2_2") (pintype "passive"))
      (node (ref "TP_USH1") (pin "X") (pinfunction "TESTP_X") (pintype "passive"))
      (node (ref "X2") (pin "P$1") (pinfunction "P$1_P$1") (pintype "bidirectional"))
      (node (ref "X2") (pin "P$2") (pinfunction "P$2_P$2") (pintype "bidirectional"))
      (node (ref "Z1") (pin "2") (pinfunction "2_2") (pintype "passive"))
      (node (ref "Z2") (pin "2") (pinfunction "2_2") (pintype "passive"))
    )
    (net (code "50") (name "/VIN") (class "Default")
      (node (ref "D1") (pin "C") (pinfunction "C_C") (pintype "passive"))
      (node (ref "PC1") (pin "+") (pinfunction "+_+") (pintype "passive"))
      (node (ref "TP_VIN1") (pin "X") (pinfunction "TESTP_X") (pintype "passive"))
      (node (ref "U1") (pin "3") (pinfunction "IN_3") (pintype "input"))
    )
    (net (code "51") (name "/XT1") (class "Default")
      (node (ref "C7") (pin "1") (pinfunction "1_1") (pintype "passive"))
      (node (ref "R1") (pin "1") (pinfunction "1_1") (pintype "passive"))
      (node (ref "TP_XT2") (pin "X") (pinfunction "TESTP_X") (pintype "passive"))
      (node (ref "U4") (pin "1") (pinfunction "XTAL1_1") (pintype "bidirectional"))
      (node (ref "Y1") (pin "2") (pinfunction "2_2") (pintype "passive"))
    )
    (net (code "52") (name "/XT2") (class "Default")
      (node (ref "C6") (pin "1") (pinfunction "1_1") (pintype "passive"))
      (node (ref "R1") (pin "2") (pinfunction "2_2") (pintype "passive"))
      (node (ref "TP_XT4") (pin "X") (pinfunction "TESTP_X") (pintype "passive"))
      (node (ref "U4") (pin "2") (pinfunction "XTAL2(PC0)_2") (pintype "bidirectional"))
      (node (ref "Y1") (pin "1") (pinfunction "1_1") (pintype "passive"))
    )
    (net (code "53") (name "/XTAL1") (class "Default")
      (node (ref "R2") (pin "1") (pinfunction "1_1") (pintype "passive"))
      (node (ref "TP_XT3") (pin "X") (pinfunction "TESTP_X") (pintype "passive"))
      (node (ref "Y2") (pin "3") (pinfunction "3_3") (pintype "passive"))
      (node (ref "ZU1") (pin "9") (pinfunction "XTAL1_9") (pintype "bidirectional"))
    )
    (net (code "54") (name "/XTAL2") (class "Default")
      (node (ref "R2") (pin "2") (pinfunction "2_2") (pintype "passive"))
      (node (ref "TP_XT1") (pin "X") (pinfunction "TESTP_X") (pintype "passive"))
      (node (ref "Y2") (pin "1") (pinfunction "1_1") (pintype "passive"))
      (node (ref "ZU1") (pin "10") (pinfunction "XTAL2_10") (pintype "bidirectional"))
    )
    (net (code "55") (name "/XUSB") (class "Default")
      (node (ref "F1") (pin "2") (pinfunction "2_2") (pintype "passive"))
      (node (ref "TP_XUSB1") (pin "X") (pinfunction "TESTP_X") (pintype "passive"))
      (node (ref "X2") (pin "1") (pinfunction "1_1") (pintype "bidirectional"))
    )
    (net (code "56") (name "GND") (class "Default")
      (node (ref "C1") (pin "1") (pinfunction "1_1") (pintype "passive"))
      (node (ref "C10") (pin "2") (pinfunction "2_2") (pintype "passive"))
      (node (ref "C2") (pin "1") (pinfunction "1_1") (pintype "passive"))
      (node (ref "C3") (pin "1") (pinfunction "1_1") (pintype "passive"))
      (node (ref "C4") (pin "1") (pinfunction "1_1") (pintype "passive"))
      (node (ref "C6") (pin "2") (pinfunction "2_2") (pintype "passive"))
      (node (ref "C7") (pin "2") (pinfunction "2_2") (pintype "passive"))
      (node (ref "C8") (pin "1") (pinfunction "1_1") (pintype "passive"))
      (node (ref "C9") (pin "1") (pinfunction "1_1") (pintype "passive"))
      (node (ref "GROUND1") (pin "1") (pinfunction "1_1") (pintype "passive"))
      (node (ref "ICSP1") (pin "6") (pinfunction "6_6") (pintype "passive"))
      (node (ref "ICSP2") (pin "6") (pinfunction "6_6") (pintype "passive"))
      (node (ref "L1") (pin "C") (pinfunction "C_C") (pintype "passive"))
      (node (ref "ON1") (pin "C") (pinfunction "C_C") (pintype "passive"))
      (node (ref "PC1") (pin "-") (pinfunction "-_-") (pintype "passive"))
      (node (ref "PC2") (pin "-") (pinfunction "-_-") (pintype "passive"))
      (node (ref "POWER1") (pin "6") (pinfunction "6_6") (pintype "passive"))
      (node (ref "POWER1") (pin "7") (pinfunction "7_7") (pintype "passive"))
      (node (ref "RESET1") (pin "1") (pinfunction "1_1") (pintype "passive"))
      (node (ref "RESET1") (pin "2") (pinfunction "2_2") (pintype "passive"))
      (node (ref "RN1") (pin "7") (pinfunction "2_7") (pintype "passive"))
      (node (ref "RN4") (pin "5") (pinfunction "2_5") (pintype "passive"))
      (node (ref "U1") (pin "1") (pinfunction "GND/ADJ_1") (pintype "input"))
      (node (ref "U2") (pin "4") (pinfunction "V-_4") (pintype "power_in"))
      (node (ref "U3") (pin "2") (pinfunction "GND_2") (pintype "power_in"))
      (node (ref "U4") (pin "3") (pinfunction "GND_3") (pintype "power_in"))
      (node (ref "U4") (pin "33") (pinfunction "PAD_33") (pintype "power_in"))
      (node (ref "X1") (pin "1") (pinfunction "1_1") (pintype "power_in"))
      (node (ref "X1") (pin "3") (pinfunction "3_3") (pintype "power_in"))
      (node (ref "Y2") (pin "2") (pinfunction "2_2") (pintype "passive"))
      (node (ref "ZU1") (pin "22") (pinfunction "AGND_22") (pintype "power_in"))
      (node (ref "ZU1") (pin "8") (pinfunction "GND_8") (pintype "power_in"))
    )
    (net (code "57") (name "Net-(RN2B-2)") (class "Default")
      (node (ref "RN2") (pin "7") (pinfunction "2_7") (pintype "passive"))
      (node (ref "RX1") (pin "A") (pinfunction "A_A") (pintype "passive"))
      (node (ref "TP_RXL1") (pin "X") (pinfunction "TESTP_X") (pintype "passive"))
    )
    (net (code "58") (name "Net-(RN2C-2)") (class "Default")
      (node (ref "ON1") (pin "A") (pinfunction "A_A") (pintype "passive"))
      (node (ref "RN2") (pin "5") (pinfunction "2_5") (pintype "passive"))
      (node (ref "RN2") (pin "6") (pinfunction "2_6") (pintype "passive"))
      (node (ref "TP_ONL1") (pin "X") (pinfunction "TESTP_X") (pintype "passive"))
    )
    (net (code "59") (name "Net-(RN4C-2)") (class "Default")
      (node (ref "RN4") (pin "6") (pinfunction "2_6") (pintype "passive"))
      (node (ref "TP_TXL1") (pin "X") (pinfunction "TESTP_X") (pintype "passive"))
      (node (ref "TX1") (pin "A") (pinfunction "A_A") (pintype "passive"))
    )
    (net (code "60") (name "Net-(TP_LL1-TESTP)") (class "Default")
      (node (ref "L1") (pin "A") (pinfunction "A_A") (pintype "passive"))
      (node (ref "RN2") (pin "1") (pinfunction "1_1") (pintype "passive"))
      (node (ref "TP_LL1") (pin "X") (pinfunction "TESTP_X") (pintype "passive"))
    )
    (net (code "61") (name "Net-(TP_USBVCC1-TESTP)") (class "Default")
      (node (ref "TP_USBVCC1") (pin "X") (pinfunction "TESTP_X") (pintype "passive"))
      (node (ref "U4") (pin "31") (pinfunction "UVCC_31") (pintype "power_in"))
    )
    (net (code "62") (name "unconnected-(F1-Pad1)") (class "Default")
      (node (ref "F1") (pin "1") (pinfunction "1_1") (pintype "passive+no_connect"))
    )
    (net (code "63") (name "unconnected-(IOH1-Pad7)") (class "Default")
      (node (ref "IOH1") (pin "7") (pinfunction "7_7") (pintype "passive+no_connect"))
    )
    (net (code "64") (name "unconnected-(ORIGIN1-TESTP-PadX)") (class "Default")
      (node (ref "ORIGIN1") (pin "X") (pinfunction "TESTP_X") (pintype "passive"))
    )
    (net (code "65") (name "unconnected-(POWER1-Pad1)") (class "Default")
      (node (ref "POWER1") (pin "1") (pinfunction "1_1") (pintype "passive"))
    )
    (net (code "66") (name "unconnected-(POWER1-Pad4)") (class "Default")
      (node (ref "POWER1") (pin "4") (pinfunction "4_4") (pintype "passive+no_connect"))
    )
    (net (code "67") (name "unconnected-(POWER1-Pad8)") (class "Default")
      (node (ref "POWER1") (pin "8") (pinfunction "8_8") (pintype "passive+no_connect"))
    )
    (net (code "68") (name "unconnected-(RESET1-5-GND-Pad5)") (class "Default")
      (node (ref "RESET1") (pin "5") (pinfunction "5-GND_5") (pintype "power_in"))
    )
    (net (code "69") (name "unconnected-(RN1A-2-Pad8)") (class "Default")
      (node (ref "RN1") (pin "8") (pinfunction "2_8") (pintype "passive+no_connect"))
    )
    (net (code "70") (name "unconnected-(RN3B-1-Pad2)") (class "Default")
      (node (ref "RN3") (pin "2") (pinfunction "1_2") (pintype "passive"))
    )
    (net (code "71") (name "unconnected-(RN3B-2-Pad7)") (class "Default")
      (node (ref "RN3") (pin "7") (pinfunction "2_7") (pintype "passive"))
    )
    (net (code "72") (name "unconnected-(RN3C-1-Pad3)") (class "Default")
      (node (ref "RN3") (pin "3") (pinfunction "1_3") (pintype "passive"))
    )
    (net (code "73") (name "unconnected-(RN3C-2-Pad6)") (class "Default")
      (node (ref "RN3") (pin "6") (pinfunction "2_6") (pintype "passive"))
    )
    (net (code "74") (name "unconnected-(T1-D-Pad1)") (class "Default")
      (node (ref "T1") (pin "1") (pinfunction "D_1") (pintype "passive+no_connect"))
    )
    (net (code "75") (name "unconnected-(U2A--IN-Pad2)") (class "Default")
      (node (ref "U2") (pin "2") (pinfunction "-IN_2") (pintype "input+no_connect"))
    )
    (net (code "76") (name "unconnected-(U2B-+IN-Pad5)") (class "Default")
      (node (ref "U2") (pin "5") (pinfunction "+IN_5") (pintype "input+no_connect"))
    )
    (net (code "77") (name "unconnected-(U3-NC{slash}FB-Pad4)") (class "Default")
      (node (ref "U3") (pin "4") (pinfunction "NC/FB_4") (pintype "passive"))
    )
    (net (code "78") (name "unconnected-(U4-(AIN0{slash}INT1)PD1-Pad7)") (class "Default")
      (node (ref "U4") (pin "7") (pinfunction "(AIN0/INT1)PD1_7") (pintype "bidirectional"))
    )
    (net (code "79") (name "unconnected-(U4-(AIN2{slash}PCINT11)PC2-Pad5)") (class "Default")
      (node (ref "U4") (pin "5") (pinfunction "(AIN2/PCINT11)PC2_5") (pintype "bidirectional"))
    )
    (net (code "80") (name "unconnected-(U4-(INT4{slash}ICP1{slash}CLK0)PC7-Pad22)") (class "Default")
      (node (ref "U4") (pin "22") (pinfunction "(INT4/ICP1/CLK0)PC7_22") (pintype "bidirectional"))
    )
    (net (code "81") (name "unconnected-(U4-(OC0B{slash}INT0)PD0-Pad6)") (class "Default")
      (node (ref "U4") (pin "6") (pinfunction "(OC0B/INT0)PD0_6") (pintype "bidirectional"))
    )
    (net (code "82") (name "unconnected-(U4-(OC1A{slash}PCINT8)PC6-Pad23)") (class "Default")
      (node (ref "U4") (pin "23") (pinfunction "(OC1A/PCINT8)PC6_23") (pintype "bidirectional"))
    )
    (net (code "83") (name "unconnected-(U4-(PCINT9{slash}OC1B)PC5-Pad25)") (class "Default")
      (node (ref "U4") (pin "25") (pinfunction "(PCINT9/OC1B)PC5_25") (pintype "bidirectional"))
    )
    (net (code "84") (name "unconnected-(U4-(PCINT10)PC4-Pad26)") (class "Default")
      (node (ref "U4") (pin "26") (pinfunction "(PCINT10)PC4_26") (pintype "bidirectional"))
    )
    (net (code "85") (name "unconnected-(U4-(RTS{slash}AIN5{slash}INT6)PD6-Pad12)") (class "Default")
      (node (ref "U4") (pin "12") (pinfunction "(RTS/AIN5/INT6)PD6_12") (pintype "bidirectional"))
    )
    (net (code "86") (name "unconnected-(U4-(SS{slash}PCINT0)PB0-Pad14)") (class "Default")
      (node (ref "U4") (pin "14") (pinfunction "(SS/PCINT0)PB0_14") (pintype "bidirectional"))
    )
    (net (code "87") (name "unconnected-(ZU1-AREF-Pad21)") (class "Default")
      (node (ref "ZU1") (pin "21") (pinfunction "AREF_21") (pintype "passive+no_connect"))
    )
  )
)
